# 13-DPLL-02.net
KiCad netlist of a schematic drawn in Altium Designer
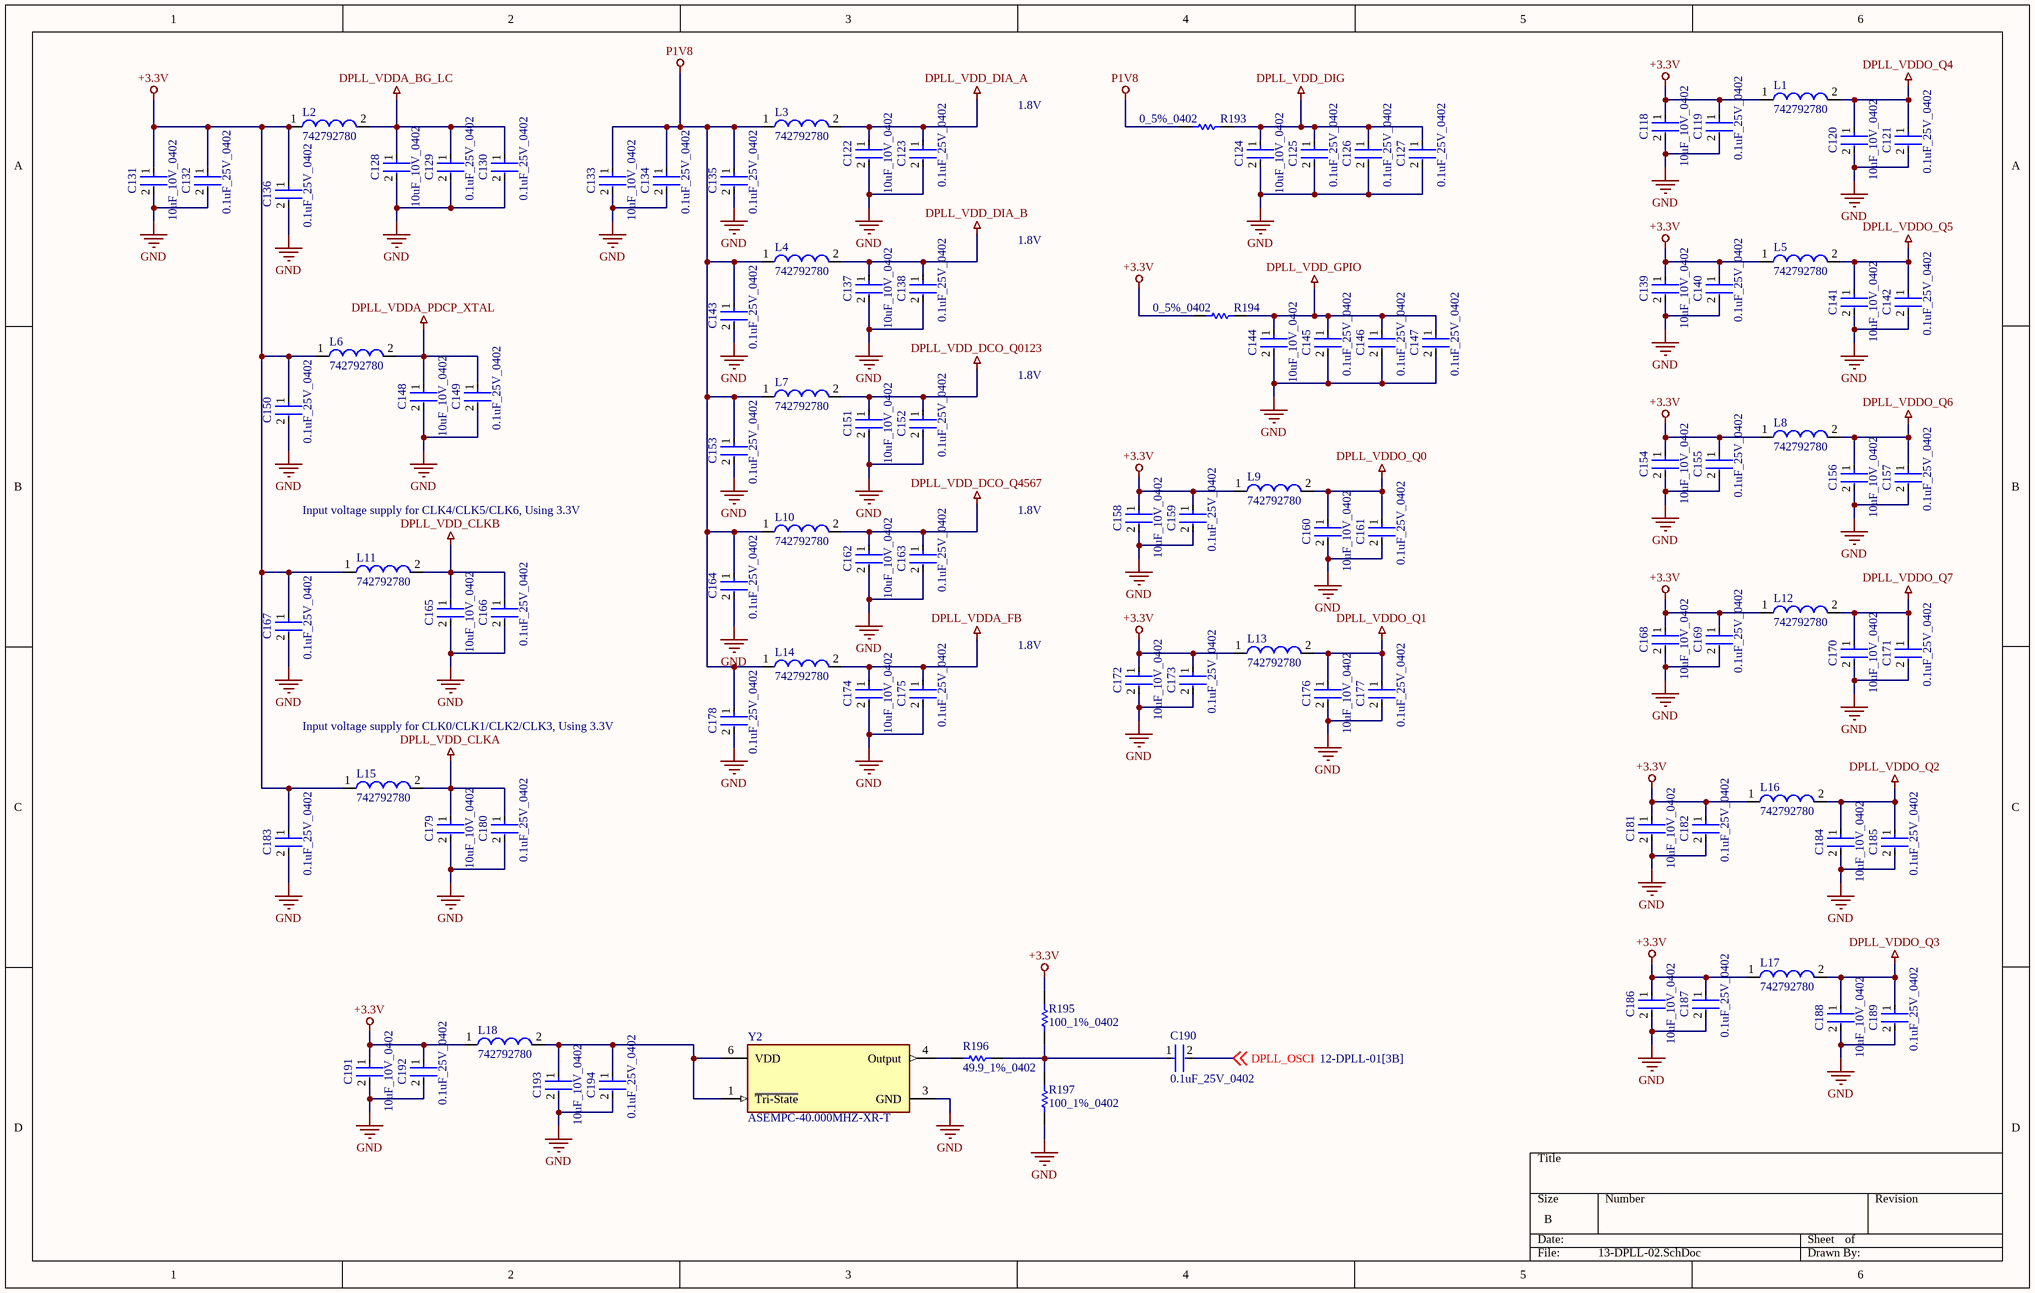
[diagram p0: 13-DPLL-02.SchDoc]

(export (version "E")
  (design (tool "Eeschema 10.0.6"))
  (components
    (comp (ref "C118")
      (value "10uF_10V_0402")
      (footprint "FP-CL05A106MP5NUNC-MFG")
      (description "CAP CER 10UF 10V X5R 0402")
      (fields
        (field (name "OCTOPART") "https://octopart.com/cl05a106mp5nunc-samsung-22457395")
        (field (name "TOLERANCE") "20%")
      )
      (libsource (lib "Altium Content Vault") (part "b4654b650e69147ec39a6b967a45e02"))
    )
    (comp (ref "C119")
      (value "0.1uF_25V_0402")
      (footprint "FP-0402-L_1_0_1-W_0_5_0_1-IPC_C")
      (description "General Purpose Ceramic Capacitor, 0402, 100nF, 10%, X7R, 15%, 25V")
      (fields (field (name "VOLTAGE") "25V") (field (name "TOLERANCE") "10%"))
      (libsource (lib "Altium Content Vault") (part "b4654b650e69147ec39a6b967a45e02"))
    )
    (comp (ref "C120")
      (value "10uF_10V_0402")
      (footprint "FP-CL05A106MP5NUNC-MFG")
      (description "CAP CER 10UF 10V X5R 0402")
      (fields
        (field (name "OCTOPART") "https://octopart.com/cl05a106mp5nunc-samsung-22457395")
        (field (name "TOLERANCE") "20%")
      )
      (libsource (lib "Altium Content Vault") (part "b4654b650e69147ec39a6b967a45e02"))
    )
    (comp (ref "C121")
      (value "0.1uF_25V_0402")
      (footprint "FP-0402-L_1_0_1-W_0_5_0_1-IPC_C")
      (description "General Purpose Ceramic Capacitor, 0402, 100nF, 10%, X7R, 15%, 25V")
      (fields (field (name "VOLTAGE") "25V") (field (name "TOLERANCE") "10%"))
      (libsource (lib "Altium Content Vault") (part "b4654b650e69147ec39a6b967a45e02"))
    )
    (comp (ref "C122")
      (value "10uF_10V_0402")
      (footprint "FP-CL05A106MP5NUNC-MFG")
      (description "CAP CER 10UF 10V X5R 0402")
      (fields
        (field (name "OCTOPART") "https://octopart.com/cl05a106mp5nunc-samsung-22457395")
        (field (name "TOLERANCE") "20%")
      )
      (libsource (lib "Altium Content Vault") (part "b4654b650e69147ec39a6b967a45e02"))
    )
    (comp (ref "C123")
      (value "0.1uF_25V_0402")
      (footprint "FP-0402-L_1_0_1-W_0_5_0_1-IPC_C")
      (description "General Purpose Ceramic Capacitor, 0402, 100nF, 10%, X7R, 15%, 25V")
      (fields (field (name "VOLTAGE") "25V") (field (name "TOLERANCE") "10%"))
      (libsource (lib "Altium Content Vault") (part "b4654b650e69147ec39a6b967a45e02"))
    )
    (comp (ref "C124")
      (value "10uF_10V_0402")
      (footprint "FP-CL05A106MP5NUNC-MFG")
      (description "CAP CER 10UF 10V X5R 0402")
      (fields
        (field (name "OCTOPART") "https://octopart.com/cl05a106mp5nunc-samsung-22457395")
        (field (name "TOLERANCE") "20%")
      )
      (libsource (lib "Altium Content Vault") (part "b4654b650e69147ec39a6b967a45e02"))
    )
    (comp (ref "C125")
      (value "0.1uF_25V_0402")
      (footprint "FP-0402-L_1_0_1-W_0_5_0_1-IPC_C")
      (description "General Purpose Ceramic Capacitor, 0402, 100nF, 10%, X7R, 15%, 25V")
      (fields (field (name "VOLTAGE") "25V") (field (name "TOLERANCE") "10%"))
      (libsource (lib "Altium Content Vault") (part "b4654b650e69147ec39a6b967a45e02"))
    )
    (comp (ref "C126")
      (value "0.1uF_25V_0402")
      (footprint "FP-0402-L_1_0_1-W_0_5_0_1-IPC_C")
      (description "General Purpose Ceramic Capacitor, 0402, 100nF, 10%, X7R, 15%, 25V")
      (fields (field (name "VOLTAGE") "25V") (field (name "TOLERANCE") "10%"))
      (libsource (lib "Altium Content Vault") (part "b4654b650e69147ec39a6b967a45e02"))
    )
    (comp (ref "C127")
      (value "0.1uF_25V_0402")
      (footprint "FP-0402-L_1_0_1-W_0_5_0_1-IPC_C")
      (description "General Purpose Ceramic Capacitor, 0402, 100nF, 10%, X7R, 15%, 25V")
      (fields (field (name "VOLTAGE") "25V") (field (name "TOLERANCE") "10%"))
      (libsource (lib "Altium Content Vault") (part "b4654b650e69147ec39a6b967a45e02"))
    )
    (comp (ref "C128")
      (value "10uF_10V_0402")
      (footprint "FP-CL05A106MP5NUNC-MFG")
      (description "CAP CER 10UF 10V X5R 0402")
      (fields
        (field (name "OCTOPART") "https://octopart.com/cl05a106mp5nunc-samsung-22457395")
        (field (name "TOLERANCE") "20%")
      )
      (libsource (lib "Altium Content Vault") (part "b4654b650e69147ec39a6b967a45e02"))
    )
    (comp (ref "C129")
      (value "0.1uF_25V_0402")
      (footprint "FP-0402-L_1_0_1-W_0_5_0_1-IPC_C")
      (description "General Purpose Ceramic Capacitor, 0402, 100nF, 10%, X7R, 15%, 25V")
      (fields (field (name "VOLTAGE") "25V") (field (name "TOLERANCE") "10%"))
      (libsource (lib "Altium Content Vault") (part "b4654b650e69147ec39a6b967a45e02"))
    )
    (comp (ref "C130")
      (value "0.1uF_25V_0402")
      (footprint "FP-0402-L_1_0_1-W_0_5_0_1-IPC_C")
      (description "General Purpose Ceramic Capacitor, 0402, 100nF, 10%, X7R, 15%, 25V")
      (fields (field (name "VOLTAGE") "25V") (field (name "TOLERANCE") "10%"))
      (libsource (lib "Altium Content Vault") (part "b4654b650e69147ec39a6b967a45e02"))
    )
    (comp (ref "C131")
      (value "10uF_10V_0402")
      (footprint "FP-CL05A106MP5NUNC-MFG")
      (description "CAP CER 10UF 10V X5R 0402")
      (fields
        (field (name "OCTOPART") "https://octopart.com/cl05a106mp5nunc-samsung-22457395")
        (field (name "TOLERANCE") "20%")
      )
      (libsource (lib "Altium Content Vault") (part "b4654b650e69147ec39a6b967a45e02"))
    )
    (comp (ref "C132")
      (value "0.1uF_25V_0402")
      (footprint "FP-0402-L_1_0_1-W_0_5_0_1-IPC_C")
      (description "General Purpose Ceramic Capacitor, 0402, 100nF, 10%, X7R, 15%, 25V")
      (fields (field (name "VOLTAGE") "25V") (field (name "TOLERANCE") "10%"))
      (libsource (lib "Altium Content Vault") (part "b4654b650e69147ec39a6b967a45e02"))
    )
    (comp (ref "C133")
      (value "10uF_10V_0402")
      (footprint "FP-CL05A106MP5NUNC-MFG")
      (description "CAP CER 10UF 10V X5R 0402")
      (fields
        (field (name "OCTOPART") "https://octopart.com/cl05a106mp5nunc-samsung-22457395")
        (field (name "TOLERANCE") "20%")
      )
      (libsource (lib "Altium Content Vault") (part "b4654b650e69147ec39a6b967a45e02"))
    )
    (comp (ref "C134")
      (value "0.1uF_25V_0402")
      (footprint "FP-0402-L_1_0_1-W_0_5_0_1-IPC_C")
      (description "General Purpose Ceramic Capacitor, 0402, 100nF, 10%, X7R, 15%, 25V")
      (fields (field (name "VOLTAGE") "25V") (field (name "TOLERANCE") "10%"))
      (libsource (lib "Altium Content Vault") (part "b4654b650e69147ec39a6b967a45e02"))
    )
    (comp (ref "C135")
      (value "0.1uF_25V_0402")
      (footprint "FP-0402-L_1_0_1-W_0_5_0_1-IPC_C")
      (description "General Purpose Ceramic Capacitor, 0402, 100nF, 10%, X7R, 15%, 25V")
      (fields (field (name "VOLTAGE") "25V") (field (name "TOLERANCE") "10%"))
      (libsource (lib "Altium Content Vault") (part "b4654b650e69147ec39a6b967a45e02"))
    )
    (comp (ref "C136")
      (value "0.1uF_25V_0402")
      (footprint "FP-0402-L_1_0_1-W_0_5_0_1-IPC_C")
      (description "General Purpose Ceramic Capacitor, 0402, 100nF, 10%, X7R, 15%, 25V")
      (fields (field (name "VOLTAGE") "25V") (field (name "TOLERANCE") "10%"))
      (libsource (lib "Altium Content Vault") (part "b4654b650e69147ec39a6b967a45e02"))
    )
    (comp (ref "C137")
      (value "10uF_10V_0402")
      (footprint "FP-CL05A106MP5NUNC-MFG")
      (description "CAP CER 10UF 10V X5R 0402")
      (fields
        (field (name "OCTOPART") "https://octopart.com/cl05a106mp5nunc-samsung-22457395")
        (field (name "TOLERANCE") "20%")
      )
      (libsource (lib "Altium Content Vault") (part "b4654b650e69147ec39a6b967a45e02"))
    )
    (comp (ref "C138")
      (value "0.1uF_25V_0402")
      (footprint "FP-0402-L_1_0_1-W_0_5_0_1-IPC_C")
      (description "General Purpose Ceramic Capacitor, 0402, 100nF, 10%, X7R, 15%, 25V")
      (fields (field (name "VOLTAGE") "25V") (field (name "TOLERANCE") "10%"))
      (libsource (lib "Altium Content Vault") (part "b4654b650e69147ec39a6b967a45e02"))
    )
    (comp (ref "C139")
      (value "10uF_10V_0402")
      (footprint "FP-CL05A106MP5NUNC-MFG")
      (description "CAP CER 10UF 10V X5R 0402")
      (fields
        (field (name "OCTOPART") "https://octopart.com/cl05a106mp5nunc-samsung-22457395")
        (field (name "TOLERANCE") "20%")
      )
      (libsource (lib "Altium Content Vault") (part "b4654b650e69147ec39a6b967a45e02"))
    )
    (comp (ref "C140")
      (value "0.1uF_25V_0402")
      (footprint "FP-0402-L_1_0_1-W_0_5_0_1-IPC_C")
      (description "General Purpose Ceramic Capacitor, 0402, 100nF, 10%, X7R, 15%, 25V")
      (fields (field (name "VOLTAGE") "25V") (field (name "TOLERANCE") "10%"))
      (libsource (lib "Altium Content Vault") (part "b4654b650e69147ec39a6b967a45e02"))
    )
    (comp (ref "C141")
      (value "10uF_10V_0402")
      (footprint "FP-CL05A106MP5NUNC-MFG")
      (description "CAP CER 10UF 10V X5R 0402")
      (fields
        (field (name "OCTOPART") "https://octopart.com/cl05a106mp5nunc-samsung-22457395")
        (field (name "TOLERANCE") "20%")
      )
      (libsource (lib "Altium Content Vault") (part "b4654b650e69147ec39a6b967a45e02"))
    )
    (comp (ref "C142")
      (value "0.1uF_25V_0402")
      (footprint "FP-0402-L_1_0_1-W_0_5_0_1-IPC_C")
      (description "General Purpose Ceramic Capacitor, 0402, 100nF, 10%, X7R, 15%, 25V")
      (fields (field (name "VOLTAGE") "25V") (field (name "TOLERANCE") "10%"))
      (libsource (lib "Altium Content Vault") (part "b4654b650e69147ec39a6b967a45e02"))
    )
    (comp (ref "C143")
      (value "0.1uF_25V_0402")
      (footprint "FP-0402-L_1_0_1-W_0_5_0_1-IPC_C")
      (description "General Purpose Ceramic Capacitor, 0402, 100nF, 10%, X7R, 15%, 25V")
      (fields (field (name "VOLTAGE") "25V") (field (name "TOLERANCE") "10%"))
      (libsource (lib "Altium Content Vault") (part "b4654b650e69147ec39a6b967a45e02"))
    )
    (comp (ref "C144")
      (value "10uF_10V_0402")
      (footprint "FP-CL05A106MP5NUNC-MFG")
      (description "CAP CER 10UF 10V X5R 0402")
      (fields
        (field (name "OCTOPART") "https://octopart.com/cl05a106mp5nunc-samsung-22457395")
        (field (name "TOLERANCE") "20%")
      )
      (libsource (lib "Altium Content Vault") (part "b4654b650e69147ec39a6b967a45e02"))
    )
    (comp (ref "C145")
      (value "0.1uF_25V_0402")
      (footprint "FP-0402-L_1_0_1-W_0_5_0_1-IPC_C")
      (description "General Purpose Ceramic Capacitor, 0402, 100nF, 10%, X7R, 15%, 25V")
      (fields (field (name "VOLTAGE") "25V") (field (name "TOLERANCE") "10%"))
      (libsource (lib "Altium Content Vault") (part "b4654b650e69147ec39a6b967a45e02"))
    )
    (comp (ref "C146")
      (value "0.1uF_25V_0402")
      (footprint "FP-0402-L_1_0_1-W_0_5_0_1-IPC_C")
      (description "General Purpose Ceramic Capacitor, 0402, 100nF, 10%, X7R, 15%, 25V")
      (fields (field (name "VOLTAGE") "25V") (field (name "TOLERANCE") "10%"))
      (libsource (lib "Altium Content Vault") (part "b4654b650e69147ec39a6b967a45e02"))
    )
    (comp (ref "C147")
      (value "0.1uF_25V_0402")
      (footprint "FP-0402-L_1_0_1-W_0_5_0_1-IPC_C")
      (description "General Purpose Ceramic Capacitor, 0402, 100nF, 10%, X7R, 15%, 25V")
      (fields (field (name "VOLTAGE") "25V") (field (name "TOLERANCE") "10%"))
      (libsource (lib "Altium Content Vault") (part "b4654b650e69147ec39a6b967a45e02"))
    )
    (comp (ref "C148")
      (value "10uF_10V_0402")
      (footprint "FP-CL05A106MP5NUNC-MFG")
      (description "CAP CER 10UF 10V X5R 0402")
      (fields
        (field (name "OCTOPART") "https://octopart.com/cl05a106mp5nunc-samsung-22457395")
        (field (name "TOLERANCE") "20%")
      )
      (libsource (lib "Altium Content Vault") (part "b4654b650e69147ec39a6b967a45e02"))
    )
    (comp (ref "C149")
      (value "0.1uF_25V_0402")
      (footprint "FP-0402-L_1_0_1-W_0_5_0_1-IPC_C")
      (description "General Purpose Ceramic Capacitor, 0402, 100nF, 10%, X7R, 15%, 25V")
      (fields (field (name "VOLTAGE") "25V") (field (name "TOLERANCE") "10%"))
      (libsource (lib "Altium Content Vault") (part "b4654b650e69147ec39a6b967a45e02"))
    )
    (comp (ref "C150")
      (value "0.1uF_25V_0402")
      (footprint "FP-0402-L_1_0_1-W_0_5_0_1-IPC_C")
      (description "General Purpose Ceramic Capacitor, 0402, 100nF, 10%, X7R, 15%, 25V")
      (fields (field (name "VOLTAGE") "25V") (field (name "TOLERANCE") "10%"))
      (libsource (lib "Altium Content Vault") (part "b4654b650e69147ec39a6b967a45e02"))
    )
    (comp (ref "C151")
      (value "10uF_10V_0402")
      (footprint "FP-CL05A106MP5NUNC-MFG")
      (description "CAP CER 10UF 10V X5R 0402")
      (fields
        (field (name "OCTOPART") "https://octopart.com/cl05a106mp5nunc-samsung-22457395")
        (field (name "TOLERANCE") "20%")
      )
      (libsource (lib "Altium Content Vault") (part "b4654b650e69147ec39a6b967a45e02"))
    )
    (comp (ref "C152")
      (value "0.1uF_25V_0402")
      (footprint "FP-0402-L_1_0_1-W_0_5_0_1-IPC_C")
      (description "General Purpose Ceramic Capacitor, 0402, 100nF, 10%, X7R, 15%, 25V")
      (fields (field (name "VOLTAGE") "25V") (field (name "TOLERANCE") "10%"))
      (libsource (lib "Altium Content Vault") (part "b4654b650e69147ec39a6b967a45e02"))
    )
    (comp (ref "C153")
      (value "0.1uF_25V_0402")
      (footprint "FP-0402-L_1_0_1-W_0_5_0_1-IPC_C")
      (description "General Purpose Ceramic Capacitor, 0402, 100nF, 10%, X7R, 15%, 25V")
      (fields (field (name "VOLTAGE") "25V") (field (name "TOLERANCE") "10%"))
      (libsource (lib "Altium Content Vault") (part "b4654b650e69147ec39a6b967a45e02"))
    )
    (comp (ref "C154")
      (value "10uF_10V_0402")
      (footprint "FP-CL05A106MP5NUNC-MFG")
      (description "CAP CER 10UF 10V X5R 0402")
      (fields
        (field (name "OCTOPART") "https://octopart.com/cl05a106mp5nunc-samsung-22457395")
        (field (name "TOLERANCE") "20%")
      )
      (libsource (lib "Altium Content Vault") (part "b4654b650e69147ec39a6b967a45e02"))
    )
    (comp (ref "C155")
      (value "0.1uF_25V_0402")
      (footprint "FP-0402-L_1_0_1-W_0_5_0_1-IPC_C")
      (description "General Purpose Ceramic Capacitor, 0402, 100nF, 10%, X7R, 15%, 25V")
      (fields (field (name "VOLTAGE") "25V") (field (name "TOLERANCE") "10%"))
      (libsource (lib "Altium Content Vault") (part "b4654b650e69147ec39a6b967a45e02"))
    )
    (comp (ref "C156")
      (value "10uF_10V_0402")
      (footprint "FP-CL05A106MP5NUNC-MFG")
      (description "CAP CER 10UF 10V X5R 0402")
      (fields
        (field (name "OCTOPART") "https://octopart.com/cl05a106mp5nunc-samsung-22457395")
        (field (name "TOLERANCE") "20%")
      )
      (libsource (lib "Altium Content Vault") (part "b4654b650e69147ec39a6b967a45e02"))
    )
    (comp (ref "C157")
      (value "0.1uF_25V_0402")
      (footprint "FP-0402-L_1_0_1-W_0_5_0_1-IPC_C")
      (description "General Purpose Ceramic Capacitor, 0402, 100nF, 10%, X7R, 15%, 25V")
      (fields (field (name "VOLTAGE") "25V") (field (name "TOLERANCE") "10%"))
      (libsource (lib "Altium Content Vault") (part "b4654b650e69147ec39a6b967a45e02"))
    )
    (comp (ref "C158")
      (value "10uF_10V_0402")
      (footprint "FP-CL05A106MP5NUNC-MFG")
      (description "CAP CER 10UF 10V X5R 0402")
      (fields
        (field (name "OCTOPART") "https://octopart.com/cl05a106mp5nunc-samsung-22457395")
        (field (name "TOLERANCE") "20%")
      )
      (libsource (lib "Altium Content Vault") (part "b4654b650e69147ec39a6b967a45e02"))
    )
    (comp (ref "C159")
      (value "0.1uF_25V_0402")
      (footprint "FP-0402-L_1_0_1-W_0_5_0_1-IPC_C")
      (description "General Purpose Ceramic Capacitor, 0402, 100nF, 10%, X7R, 15%, 25V")
      (fields (field (name "VOLTAGE") "25V") (field (name "TOLERANCE") "10%"))
      (libsource (lib "Altium Content Vault") (part "b4654b650e69147ec39a6b967a45e02"))
    )
    (comp (ref "C160")
      (value "10uF_10V_0402")
      (footprint "FP-CL05A106MP5NUNC-MFG")
      (description "CAP CER 10UF 10V X5R 0402")
      (fields
        (field (name "OCTOPART") "https://octopart.com/cl05a106mp5nunc-samsung-22457395")
        (field (name "TOLERANCE") "20%")
      )
      (libsource (lib "Altium Content Vault") (part "b4654b650e69147ec39a6b967a45e02"))
    )
    (comp (ref "C161")
      (value "0.1uF_25V_0402")
      (footprint "FP-0402-L_1_0_1-W_0_5_0_1-IPC_C")
      (description "General Purpose Ceramic Capacitor, 0402, 100nF, 10%, X7R, 15%, 25V")
      (fields (field (name "VOLTAGE") "25V") (field (name "TOLERANCE") "10%"))
      (libsource (lib "Altium Content Vault") (part "b4654b650e69147ec39a6b967a45e02"))
    )
    (comp (ref "C162")
      (value "10uF_10V_0402")
      (footprint "FP-CL05A106MP5NUNC-MFG")
      (description "CAP CER 10UF 10V X5R 0402")
      (fields
        (field (name "OCTOPART") "https://octopart.com/cl05a106mp5nunc-samsung-22457395")
        (field (name "TOLERANCE") "20%")
      )
      (libsource (lib "Altium Content Vault") (part "b4654b650e69147ec39a6b967a45e02"))
    )
    (comp (ref "C163")
      (value "0.1uF_25V_0402")
      (footprint "FP-0402-L_1_0_1-W_0_5_0_1-IPC_C")
      (description "General Purpose Ceramic Capacitor, 0402, 100nF, 10%, X7R, 15%, 25V")
      (fields (field (name "VOLTAGE") "25V") (field (name "TOLERANCE") "10%"))
      (libsource (lib "Altium Content Vault") (part "b4654b650e69147ec39a6b967a45e02"))
    )
    (comp (ref "C164")
      (value "0.1uF_25V_0402")
      (footprint "FP-0402-L_1_0_1-W_0_5_0_1-IPC_C")
      (description "General Purpose Ceramic Capacitor, 0402, 100nF, 10%, X7R, 15%, 25V")
      (fields (field (name "VOLTAGE") "25V") (field (name "TOLERANCE") "10%"))
      (libsource (lib "Altium Content Vault") (part "b4654b650e69147ec39a6b967a45e02"))
    )
    (comp (ref "C165")
      (value "10uF_10V_0402")
      (footprint "FP-CL05A106MP5NUNC-MFG")
      (description "CAP CER 10UF 10V X5R 0402")
      (fields
        (field (name "OCTOPART") "https://octopart.com/cl05a106mp5nunc-samsung-22457395")
        (field (name "TOLERANCE") "20%")
      )
      (libsource (lib "Altium Content Vault") (part "b4654b650e69147ec39a6b967a45e02"))
    )
    (comp (ref "C166")
      (value "0.1uF_25V_0402")
      (footprint "FP-0402-L_1_0_1-W_0_5_0_1-IPC_C")
      (description "General Purpose Ceramic Capacitor, 0402, 100nF, 10%, X7R, 15%, 25V")
      (fields (field (name "VOLTAGE") "25V") (field (name "TOLERANCE") "10%"))
      (libsource (lib "Altium Content Vault") (part "b4654b650e69147ec39a6b967a45e02"))
    )
    (comp (ref "C167")
      (value "0.1uF_25V_0402")
      (footprint "FP-0402-L_1_0_1-W_0_5_0_1-IPC_C")
      (description "General Purpose Ceramic Capacitor, 0402, 100nF, 10%, X7R, 15%, 25V")
      (fields (field (name "VOLTAGE") "25V") (field (name "TOLERANCE") "10%"))
      (libsource (lib "Altium Content Vault") (part "b4654b650e69147ec39a6b967a45e02"))
    )
    (comp (ref "C168")
      (value "10uF_10V_0402")
      (footprint "FP-CL05A106MP5NUNC-MFG")
      (description "CAP CER 10UF 10V X5R 0402")
      (fields
        (field (name "OCTOPART") "https://octopart.com/cl05a106mp5nunc-samsung-22457395")
        (field (name "TOLERANCE") "20%")
      )
      (libsource (lib "Altium Content Vault") (part "b4654b650e69147ec39a6b967a45e02"))
    )
    (comp (ref "C169")
      (value "0.1uF_25V_0402")
      (footprint "FP-0402-L_1_0_1-W_0_5_0_1-IPC_C")
      (description "General Purpose Ceramic Capacitor, 0402, 100nF, 10%, X7R, 15%, 25V")
      (fields (field (name "VOLTAGE") "25V") (field (name "TOLERANCE") "10%"))
      (libsource (lib "Altium Content Vault") (part "b4654b650e69147ec39a6b967a45e02"))
    )
    (comp (ref "C170")
      (value "10uF_10V_0402")
      (footprint "FP-CL05A106MP5NUNC-MFG")
      (description "CAP CER 10UF 10V X5R 0402")
      (fields
        (field (name "OCTOPART") "https://octopart.com/cl05a106mp5nunc-samsung-22457395")
        (field (name "TOLERANCE") "20%")
      )
      (libsource (lib "Altium Content Vault") (part "b4654b650e69147ec39a6b967a45e02"))
    )
    (comp (ref "C171")
      (value "0.1uF_25V_0402")
      (footprint "FP-0402-L_1_0_1-W_0_5_0_1-IPC_C")
      (description "General Purpose Ceramic Capacitor, 0402, 100nF, 10%, X7R, 15%, 25V")
      (fields (field (name "VOLTAGE") "25V") (field (name "TOLERANCE") "10%"))
      (libsource (lib "Altium Content Vault") (part "b4654b650e69147ec39a6b967a45e02"))
    )
    (comp (ref "C172")
      (value "10uF_10V_0402")
      (footprint "FP-CL05A106MP5NUNC-MFG")
      (description "CAP CER 10UF 10V X5R 0402")
      (fields
        (field (name "OCTOPART") "https://octopart.com/cl05a106mp5nunc-samsung-22457395")
        (field (name "TOLERANCE") "20%")
      )
      (libsource (lib "Altium Content Vault") (part "b4654b650e69147ec39a6b967a45e02"))
    )
    (comp (ref "C173")
      (value "0.1uF_25V_0402")
      (footprint "FP-0402-L_1_0_1-W_0_5_0_1-IPC_C")
      (description "General Purpose Ceramic Capacitor, 0402, 100nF, 10%, X7R, 15%, 25V")
      (fields (field (name "VOLTAGE") "25V") (field (name "TOLERANCE") "10%"))
      (libsource (lib "Altium Content Vault") (part "b4654b650e69147ec39a6b967a45e02"))
    )
    (comp (ref "C174")
      (value "10uF_10V_0402")
      (footprint "FP-CL05A106MP5NUNC-MFG")
      (description "CAP CER 10UF 10V X5R 0402")
      (fields
        (field (name "OCTOPART") "https://octopart.com/cl05a106mp5nunc-samsung-22457395")
        (field (name "TOLERANCE") "20%")
      )
      (libsource (lib "Altium Content Vault") (part "b4654b650e69147ec39a6b967a45e02"))
    )
    (comp (ref "C175")
      (value "0.1uF_25V_0402")
      (footprint "FP-0402-L_1_0_1-W_0_5_0_1-IPC_C")
      (description "General Purpose Ceramic Capacitor, 0402, 100nF, 10%, X7R, 15%, 25V")
      (fields (field (name "VOLTAGE") "25V") (field (name "TOLERANCE") "10%"))
      (libsource (lib "Altium Content Vault") (part "b4654b650e69147ec39a6b967a45e02"))
    )
    (comp (ref "C176")
      (value "10uF_10V_0402")
      (footprint "FP-CL05A106MP5NUNC-MFG")
      (description "CAP CER 10UF 10V X5R 0402")
      (fields
        (field (name "OCTOPART") "https://octopart.com/cl05a106mp5nunc-samsung-22457395")
        (field (name "TOLERANCE") "20%")
      )
      (libsource (lib "Altium Content Vault") (part "b4654b650e69147ec39a6b967a45e02"))
    )
    (comp (ref "C177")
      (value "0.1uF_25V_0402")
      (footprint "FP-0402-L_1_0_1-W_0_5_0_1-IPC_C")
      (description "General Purpose Ceramic Capacitor, 0402, 100nF, 10%, X7R, 15%, 25V")
      (fields (field (name "VOLTAGE") "25V") (field (name "TOLERANCE") "10%"))
      (libsource (lib "Altium Content Vault") (part "b4654b650e69147ec39a6b967a45e02"))
    )
    (comp (ref "C178")
      (value "0.1uF_25V_0402")
      (footprint "FP-0402-L_1_0_1-W_0_5_0_1-IPC_C")
      (description "General Purpose Ceramic Capacitor, 0402, 100nF, 10%, X7R, 15%, 25V")
      (fields (field (name "VOLTAGE") "25V") (field (name "TOLERANCE") "10%"))
      (libsource (lib "Altium Content Vault") (part "b4654b650e69147ec39a6b967a45e02"))
    )
    (comp (ref "C179")
      (value "10uF_10V_0402")
      (footprint "FP-CL05A106MP5NUNC-MFG")
      (description "CAP CER 10UF 10V X5R 0402")
      (fields
        (field (name "OCTOPART") "https://octopart.com/cl05a106mp5nunc-samsung-22457395")
        (field (name "TOLERANCE") "20%")
      )
      (libsource (lib "Altium Content Vault") (part "b4654b650e69147ec39a6b967a45e02"))
    )
    (comp (ref "C180")
      (value "0.1uF_25V_0402")
      (footprint "FP-0402-L_1_0_1-W_0_5_0_1-IPC_C")
      (description "General Purpose Ceramic Capacitor, 0402, 100nF, 10%, X7R, 15%, 25V")
      (fields (field (name "VOLTAGE") "25V") (field (name "TOLERANCE") "10%"))
      (libsource (lib "Altium Content Vault") (part "b4654b650e69147ec39a6b967a45e02"))
    )
    (comp (ref "C181")
      (value "10uF_10V_0402")
      (footprint "FP-CL05A106MP5NUNC-MFG")
      (description "CAP CER 10UF 10V X5R 0402")
      (fields
        (field (name "OCTOPART") "https://octopart.com/cl05a106mp5nunc-samsung-22457395")
        (field (name "TOLERANCE") "20%")
      )
      (libsource (lib "Altium Content Vault") (part "b4654b650e69147ec39a6b967a45e02"))
    )
    (comp (ref "C182")
      (value "0.1uF_25V_0402")
      (footprint "FP-0402-L_1_0_1-W_0_5_0_1-IPC_C")
      (description "General Purpose Ceramic Capacitor, 0402, 100nF, 10%, X7R, 15%, 25V")
      (fields (field (name "VOLTAGE") "25V") (field (name "TOLERANCE") "10%"))
      (libsource (lib "Altium Content Vault") (part "b4654b650e69147ec39a6b967a45e02"))
    )
    (comp (ref "C183")
      (value "0.1uF_25V_0402")
      (footprint "FP-0402-L_1_0_1-W_0_5_0_1-IPC_C")
      (description "General Purpose Ceramic Capacitor, 0402, 100nF, 10%, X7R, 15%, 25V")
      (fields (field (name "VOLTAGE") "25V") (field (name "TOLERANCE") "10%"))
      (libsource (lib "Altium Content Vault") (part "b4654b650e69147ec39a6b967a45e02"))
    )
    (comp (ref "C184")
      (value "10uF_10V_0402")
      (footprint "FP-CL05A106MP5NUNC-MFG")
      (description "CAP CER 10UF 10V X5R 0402")
      (fields
        (field (name "OCTOPART") "https://octopart.com/cl05a106mp5nunc-samsung-22457395")
        (field (name "TOLERANCE") "20%")
      )
      (libsource (lib "Altium Content Vault") (part "b4654b650e69147ec39a6b967a45e02"))
    )
    (comp (ref "C185")
      (value "0.1uF_25V_0402")
      (footprint "FP-0402-L_1_0_1-W_0_5_0_1-IPC_C")
      (description "General Purpose Ceramic Capacitor, 0402, 100nF, 10%, X7R, 15%, 25V")
      (fields (field (name "VOLTAGE") "25V") (field (name "TOLERANCE") "10%"))
      (libsource (lib "Altium Content Vault") (part "b4654b650e69147ec39a6b967a45e02"))
    )
    (comp (ref "C186")
      (value "10uF_10V_0402")
      (footprint "FP-CL05A106MP5NUNC-MFG")
      (description "CAP CER 10UF 10V X5R 0402")
      (fields
        (field (name "OCTOPART") "https://octopart.com/cl05a106mp5nunc-samsung-22457395")
        (field (name "TOLERANCE") "20%")
      )
      (libsource (lib "Altium Content Vault") (part "b4654b650e69147ec39a6b967a45e02"))
    )
    (comp (ref "C187")
      (value "0.1uF_25V_0402")
      (footprint "FP-0402-L_1_0_1-W_0_5_0_1-IPC_C")
      (description "General Purpose Ceramic Capacitor, 0402, 100nF, 10%, X7R, 15%, 25V")
      (fields (field (name "VOLTAGE") "25V") (field (name "TOLERANCE") "10%"))
      (libsource (lib "Altium Content Vault") (part "b4654b650e69147ec39a6b967a45e02"))
    )
    (comp (ref "C188")
      (value "10uF_10V_0402")
      (footprint "FP-CL05A106MP5NUNC-MFG")
      (description "CAP CER 10UF 10V X5R 0402")
      (fields
        (field (name "OCTOPART") "https://octopart.com/cl05a106mp5nunc-samsung-22457395")
        (field (name "TOLERANCE") "20%")
      )
      (libsource (lib "Altium Content Vault") (part "b4654b650e69147ec39a6b967a45e02"))
    )
    (comp (ref "C189")
      (value "0.1uF_25V_0402")
      (footprint "FP-0402-L_1_0_1-W_0_5_0_1-IPC_C")
      (description "General Purpose Ceramic Capacitor, 0402, 100nF, 10%, X7R, 15%, 25V")
      (fields (field (name "VOLTAGE") "25V") (field (name "TOLERANCE") "10%"))
      (libsource (lib "Altium Content Vault") (part "b4654b650e69147ec39a6b967a45e02"))
    )
    (comp (ref "C190")
      (value "0.1uF_25V_0402")
      (footprint "FP-0402-L_1_0_1-W_0_5_0_1-IPC_C")
      (description "General Purpose Ceramic Capacitor, 0402, 100nF, 10%, X7R, 15%, 25V")
      (fields (field (name "VOLTAGE") "25V") (field (name "TOLERANCE") "10%"))
      (libsource (lib "Altium Content Vault") (part "b4654b650e69147ec39a6b967a45e02"))
    )
    (comp (ref "C191")
      (value "10uF_10V_0402")
      (footprint "FP-CL05A106MP5NUNC-MFG")
      (description "CAP CER 10UF 10V X5R 0402")
      (fields
        (field (name "OCTOPART") "https://octopart.com/cl05a106mp5nunc-samsung-22457395")
        (field (name "TOLERANCE") "20%")
      )
      (libsource (lib "Altium Content Vault") (part "b4654b650e69147ec39a6b967a45e02"))
    )
    (comp (ref "C192")
      (value "0.1uF_25V_0402")
      (footprint "FP-0402-L_1_0_1-W_0_5_0_1-IPC_C")
      (description "General Purpose Ceramic Capacitor, 0402, 100nF, 10%, X7R, 15%, 25V")
      (fields (field (name "VOLTAGE") "25V") (field (name "TOLERANCE") "10%"))
      (libsource (lib "Altium Content Vault") (part "b4654b650e69147ec39a6b967a45e02"))
    )
    (comp (ref "C193")
      (value "10uF_10V_0402")
      (footprint "FP-CL05A106MP5NUNC-MFG")
      (description "CAP CER 10UF 10V X5R 0402")
      (fields
        (field (name "OCTOPART") "https://octopart.com/cl05a106mp5nunc-samsung-22457395")
        (field (name "TOLERANCE") "20%")
      )
      (libsource (lib "Altium Content Vault") (part "b4654b650e69147ec39a6b967a45e02"))
    )
    (comp (ref "C194")
      (value "0.1uF_25V_0402")
      (footprint "FP-0402-L_1_0_1-W_0_5_0_1-IPC_C")
      (description "General Purpose Ceramic Capacitor, 0402, 100nF, 10%, X7R, 15%, 25V")
      (fields (field (name "VOLTAGE") "25V") (field (name "TOLERANCE") "10%"))
      (libsource (lib "Altium Content Vault") (part "b4654b650e69147ec39a6b967a45e02"))
    )
    (comp (ref "L1")
      (value "742792780")
      (footprint "SMD-0402")
      (description "SMD EMI Suppression Ferrite Bead WE-CBF, Z = 220 Ohm")
      (libsource (lib "Altium Content Vault") (part "PAS-IND-INDUCTOR-2"))
    )
    (comp (ref "L2")
      (value "742792780")
      (footprint "SMD-0402")
      (description "SMD EMI Suppression Ferrite Bead WE-CBF, Z = 220 Ohm")
      (libsource (lib "Altium Content Vault") (part "PAS-IND-INDUCTOR-2"))
    )
    (comp (ref "L3")
      (value "742792780")
      (footprint "SMD-0402")
      (description "SMD EMI Suppression Ferrite Bead WE-CBF, Z = 220 Ohm")
      (libsource (lib "Altium Content Vault") (part "PAS-IND-INDUCTOR-2"))
    )
    (comp (ref "L4")
      (value "742792780")
      (footprint "SMD-0402")
      (description "SMD EMI Suppression Ferrite Bead WE-CBF, Z = 220 Ohm")
      (libsource (lib "Altium Content Vault") (part "PAS-IND-INDUCTOR-2"))
    )
    (comp (ref "L5")
      (value "742792780")
      (footprint "SMD-0402")
      (description "SMD EMI Suppression Ferrite Bead WE-CBF, Z = 220 Ohm")
      (libsource (lib "Altium Content Vault") (part "PAS-IND-INDUCTOR-2"))
    )
    (comp (ref "L6")
      (value "742792780")
      (footprint "SMD-0402")
      (description "SMD EMI Suppression Ferrite Bead WE-CBF, Z = 220 Ohm")
      (libsource (lib "Altium Content Vault") (part "PAS-IND-INDUCTOR-2"))
    )
    (comp (ref "L7")
      (value "742792780")
      (footprint "SMD-0402")
      (description "SMD EMI Suppression Ferrite Bead WE-CBF, Z = 220 Ohm")
      (libsource (lib "Altium Content Vault") (part "PAS-IND-INDUCTOR-2"))
    )
    (comp (ref "L8")
      (value "742792780")
      (footprint "SMD-0402")
      (description "SMD EMI Suppression Ferrite Bead WE-CBF, Z = 220 Ohm")
      (libsource (lib "Altium Content Vault") (part "PAS-IND-INDUCTOR-2"))
    )
    (comp (ref "L9")
      (value "742792780")
      (footprint "SMD-0402")
      (description "SMD EMI Suppression Ferrite Bead WE-CBF, Z = 220 Ohm")
      (libsource (lib "Altium Content Vault") (part "PAS-IND-INDUCTOR-2"))
    )
    (comp (ref "L10")
      (value "742792780")
      (footprint "SMD-0402")
      (description "SMD EMI Suppression Ferrite Bead WE-CBF, Z = 220 Ohm")
      (libsource (lib "Altium Content Vault") (part "PAS-IND-INDUCTOR-2"))
    )
    (comp (ref "L11")
      (value "742792780")
      (footprint "SMD-0402")
      (description "SMD EMI Suppression Ferrite Bead WE-CBF, Z = 220 Ohm")
      (libsource (lib "Altium Content Vault") (part "PAS-IND-INDUCTOR-2"))
    )
    (comp (ref "L12")
      (value "742792780")
      (footprint "SMD-0402")
      (description "SMD EMI Suppression Ferrite Bead WE-CBF, Z = 220 Ohm")
      (libsource (lib "Altium Content Vault") (part "PAS-IND-INDUCTOR-2"))
    )
    (comp (ref "L13")
      (value "742792780")
      (footprint "SMD-0402")
      (description "SMD EMI Suppression Ferrite Bead WE-CBF, Z = 220 Ohm")
      (libsource (lib "Altium Content Vault") (part "PAS-IND-INDUCTOR-2"))
    )
    (comp (ref "L14")
      (value "742792780")
      (footprint "SMD-0402")
      (description "SMD EMI Suppression Ferrite Bead WE-CBF, Z = 220 Ohm")
      (libsource (lib "Altium Content Vault") (part "PAS-IND-INDUCTOR-2"))
    )
    (comp (ref "L15")
      (value "742792780")
      (footprint "SMD-0402")
      (description "SMD EMI Suppression Ferrite Bead WE-CBF, Z = 220 Ohm")
      (libsource (lib "Altium Content Vault") (part "PAS-IND-INDUCTOR-2"))
    )
    (comp (ref "L16")
      (value "742792780")
      (footprint "SMD-0402")
      (description "SMD EMI Suppression Ferrite Bead WE-CBF, Z = 220 Ohm")
      (libsource (lib "Altium Content Vault") (part "PAS-IND-INDUCTOR-2"))
    )
    (comp (ref "L17")
      (value "742792780")
      (footprint "SMD-0402")
      (description "SMD EMI Suppression Ferrite Bead WE-CBF, Z = 220 Ohm")
      (libsource (lib "Altium Content Vault") (part "PAS-IND-INDUCTOR-2"))
    )
    (comp (ref "L18")
      (value "742792780")
      (footprint "SMD-0402")
      (description "SMD EMI Suppression Ferrite Bead WE-CBF, Z = 220 Ohm")
      (libsource (lib "Altium Content Vault") (part "PAS-IND-INDUCTOR-2"))
    )
    (comp (ref "R193")
      (value "0_5%_0402")
      (footprint "RESC1005X40X25LL10T10")
      (fields (field (name "MANUFACTURER") "KOA Speer") (field (name "PART NUMBER") "RK73Z1ETTP"))
      (libsource (lib "Altium Content Vault") (part "RES"))
    )
    (comp (ref "R194")
      (value "0_5%_0402")
      (footprint "RESC1005X40X25LL10T10")
      (fields (field (name "MANUFACTURER") "KOA Speer") (field (name "PART NUMBER") "RK73Z1ETTP"))
      (libsource (lib "Altium Content Vault") (part "RES"))
    )
    (comp (ref "R195")
      (value "100_1%_0402")
      (footprint "RESC1005X40X25ML05T10")
      (fields (field (name "PART NUMBER") "ERJ-U02F1000X") (field (name "MANUFACTURER") "Panasonic"))
      (libsource (lib "Altium Content Vault") (part "RES"))
    )
    (comp (ref "R196")
      (value "49.9_1%_0402")
      (footprint "RESC1005X40X25NL10T10")
      (fields (field (name "PART NUMBER") "RK73H1ETTP49R9F") (field (name "MANUFACTURER") "KOA Speer"))
      (libsource (lib "Altium Content Vault") (part "RES"))
    )
    (comp (ref "R197")
      (value "100_1%_0402")
      (footprint "RESC1005X40X25ML05T10")
      (fields (field (name "PART NUMBER") "ERJ-U02F1000X") (field (name "MANUFACTURER") "Panasonic"))
      (libsource (lib "Altium Content Vault") (part "RES"))
    )
    (comp (ref "Y2")
      (value "ASEMPC-40.000MHZ-XR-T")
      (footprint "FP-ASEMP-CMOS-MFG")
      (description "MEMS Oscillator 40MHz ±25ppm CMOS 2.25V~3.6V 6-SMD 3.2mm x 2.5mm")
      (libsource (lib "Altium Content Vault") (part "9526c112e3a98a1af86e8f4e974a861"))
    )
  )
  (nets
    (net (code "1") (name "+3.3V") (class "Default")
      (node (ref "C118") (pin "1") (pinfunction "1_1") (pintype "passive"))
      (node (ref "C119") (pin "1") (pinfunction "1_1") (pintype "passive"))
      (node (ref "C131") (pin "1") (pinfunction "1_1") (pintype "passive"))
      (node (ref "C132") (pin "1") (pinfunction "1_1") (pintype "passive"))
      (node (ref "C136") (pin "1") (pinfunction "1_1") (pintype "passive"))
      (node (ref "C139") (pin "1") (pinfunction "1_1") (pintype "passive"))
      (node (ref "C140") (pin "1") (pinfunction "1_1") (pintype "passive"))
      (node (ref "C150") (pin "1") (pinfunction "1_1") (pintype "passive"))
      (node (ref "C154") (pin "1") (pinfunction "1_1") (pintype "passive"))
      (node (ref "C155") (pin "1") (pinfunction "1_1") (pintype "passive"))
      (node (ref "C158") (pin "1") (pinfunction "1_1") (pintype "passive"))
      (node (ref "C159") (pin "1") (pinfunction "1_1") (pintype "passive"))
      (node (ref "C167") (pin "1") (pinfunction "1_1") (pintype "passive"))
      (node (ref "C168") (pin "1") (pinfunction "1_1") (pintype "passive"))
      (node (ref "C169") (pin "1") (pinfunction "1_1") (pintype "passive"))
      (node (ref "C172") (pin "1") (pinfunction "1_1") (pintype "passive"))
      (node (ref "C173") (pin "1") (pinfunction "1_1") (pintype "passive"))
      (node (ref "C181") (pin "1") (pinfunction "1_1") (pintype "passive"))
      (node (ref "C182") (pin "1") (pinfunction "1_1") (pintype "passive"))
      (node (ref "C183") (pin "1") (pinfunction "1_1") (pintype "passive"))
      (node (ref "C186") (pin "1") (pinfunction "1_1") (pintype "passive"))
      (node (ref "C187") (pin "1") (pinfunction "1_1") (pintype "passive"))
      (node (ref "C191") (pin "1") (pinfunction "1_1") (pintype "passive"))
      (node (ref "C192") (pin "1") (pinfunction "1_1") (pintype "passive"))
      (node (ref "L1") (pin "1") (pinfunction "1_1") (pintype "passive"))
      (node (ref "L11") (pin "1") (pinfunction "1_1") (pintype "passive"))
      (node (ref "L12") (pin "1") (pinfunction "1_1") (pintype "passive"))
      (node (ref "L13") (pin "1") (pinfunction "1_1") (pintype "passive"))
      (node (ref "L15") (pin "1") (pinfunction "1_1") (pintype "passive"))
      (node (ref "L16") (pin "1") (pinfunction "1_1") (pintype "passive"))
      (node (ref "L17") (pin "1") (pinfunction "1_1") (pintype "passive"))
      (node (ref "L18") (pin "1") (pinfunction "1_1") (pintype "passive"))
      (node (ref "L2") (pin "1") (pinfunction "1_1") (pintype "passive"))
      (node (ref "L5") (pin "1") (pinfunction "1_1") (pintype "passive"))
      (node (ref "L6") (pin "1") (pinfunction "1_1") (pintype "passive"))
      (node (ref "L8") (pin "1") (pinfunction "1_1") (pintype "passive"))
      (node (ref "L9") (pin "1") (pinfunction "1_1") (pintype "passive"))
      (node (ref "R194") (pin "1") (pinfunction "1_1") (pintype "passive"))
      (node (ref "R195") (pin "2") (pinfunction "2_2") (pintype "passive"))
    )
    (net (code "2") (name "DPLL_OSCI") (class "Default")
      (node (ref "C190") (pin "2") (pinfunction "2_2") (pintype "passive"))
    )
    (net (code "3") (name "DPLL_VDDA_BG_LC") (class "Default")
      (node (ref "C128") (pin "1") (pinfunction "1_1") (pintype "passive"))
      (node (ref "C129") (pin "1") (pinfunction "1_1") (pintype "passive"))
      (node (ref "C130") (pin "1") (pinfunction "1_1") (pintype "passive"))
      (node (ref "L2") (pin "2") (pinfunction "2_2") (pintype "passive"))
    )
    (net (code "4") (name "DPLL_VDDA_FB") (class "Default")
      (node (ref "C174") (pin "1") (pinfunction "1_1") (pintype "passive"))
      (node (ref "C175") (pin "1") (pinfunction "1_1") (pintype "passive"))
      (node (ref "L14") (pin "2") (pinfunction "2_2") (pintype "passive"))
    )
    (net (code "5") (name "DPLL_VDDA_PDCP_XTAL") (class "Default")
      (node (ref "C148") (pin "1") (pinfunction "1_1") (pintype "passive"))
      (node (ref "C149") (pin "1") (pinfunction "1_1") (pintype "passive"))
      (node (ref "L6") (pin "2") (pinfunction "2_2") (pintype "passive"))
    )
    (net (code "6") (name "DPLL_VDDO_Q0") (class "Default")
      (node (ref "C160") (pin "1") (pinfunction "1_1") (pintype "passive"))
      (node (ref "C161") (pin "1") (pinfunction "1_1") (pintype "passive"))
      (node (ref "L9") (pin "2") (pinfunction "2_2") (pintype "passive"))
    )
    (net (code "7") (name "DPLL_VDDO_Q1") (class "Default")
      (node (ref "C176") (pin "1") (pinfunction "1_1") (pintype "passive"))
      (node (ref "C177") (pin "1") (pinfunction "1_1") (pintype "passive"))
      (node (ref "L13") (pin "2") (pinfunction "2_2") (pintype "passive"))
    )
    (net (code "8") (name "DPLL_VDDO_Q2") (class "Default")
      (node (ref "C184") (pin "1") (pinfunction "1_1") (pintype "passive"))
      (node (ref "C185") (pin "1") (pinfunction "1_1") (pintype "passive"))
      (node (ref "L16") (pin "2") (pinfunction "2_2") (pintype "passive"))
    )
    (net (code "9") (name "DPLL_VDDO_Q3") (class "Default")
      (node (ref "C188") (pin "1") (pinfunction "1_1") (pintype "passive"))
      (node (ref "C189") (pin "1") (pinfunction "1_1") (pintype "passive"))
      (node (ref "L17") (pin "2") (pinfunction "2_2") (pintype "passive"))
    )
    (net (code "10") (name "DPLL_VDDO_Q4") (class "Default")
      (node (ref "C120") (pin "1") (pinfunction "1_1") (pintype "passive"))
      (node (ref "C121") (pin "1") (pinfunction "1_1") (pintype "passive"))
      (node (ref "L1") (pin "2") (pinfunction "2_2") (pintype "passive"))
    )
    (net (code "11") (name "DPLL_VDDO_Q5") (class "Default")
      (node (ref "C141") (pin "1") (pinfunction "1_1") (pintype "passive"))
      (node (ref "C142") (pin "1") (pinfunction "1_1") (pintype "passive"))
      (node (ref "L5") (pin "2") (pinfunction "2_2") (pintype "passive"))
    )
    (net (code "12") (name "DPLL_VDDO_Q6") (class "Default")
      (node (ref "C156") (pin "1") (pinfunction "1_1") (pintype "passive"))
      (node (ref "C157") (pin "1") (pinfunction "1_1") (pintype "passive"))
      (node (ref "L8") (pin "2") (pinfunction "2_2") (pintype "passive"))
    )
    (net (code "13") (name "DPLL_VDDO_Q7") (class "Default")
      (node (ref "C170") (pin "1") (pinfunction "1_1") (pintype "passive"))
      (node (ref "C171") (pin "1") (pinfunction "1_1") (pintype "passive"))
      (node (ref "L12") (pin "2") (pinfunction "2_2") (pintype "passive"))
    )
    (net (code "14") (name "DPLL_VDD_CLKA") (class "Default")
      (node (ref "C179") (pin "1") (pinfunction "1_1") (pintype "passive"))
      (node (ref "C180") (pin "1") (pinfunction "1_1") (pintype "passive"))
      (node (ref "L15") (pin "2") (pinfunction "2_2") (pintype "passive"))
    )
    (net (code "15") (name "DPLL_VDD_CLKB") (class "Default")
      (node (ref "C165") (pin "1") (pinfunction "1_1") (pintype "passive"))
      (node (ref "C166") (pin "1") (pinfunction "1_1") (pintype "passive"))
      (node (ref "L11") (pin "2") (pinfunction "2_2") (pintype "passive"))
    )
    (net (code "16") (name "DPLL_VDD_DCO_Q0123") (class "Default")
      (node (ref "C151") (pin "1") (pinfunction "1_1") (pintype "passive"))
      (node (ref "C152") (pin "1") (pinfunction "1_1") (pintype "passive"))
      (node (ref "L7") (pin "2") (pinfunction "2_2") (pintype "passive"))
    )
    (net (code "17") (name "DPLL_VDD_DCO_Q4567") (class "Default")
      (node (ref "C162") (pin "1") (pinfunction "1_1") (pintype "passive"))
      (node (ref "C163") (pin "1") (pinfunction "1_1") (pintype "passive"))
      (node (ref "L10") (pin "2") (pinfunction "2_2") (pintype "passive"))
    )
    (net (code "18") (name "DPLL_VDD_DIA_A") (class "Default")
      (node (ref "C122") (pin "1") (pinfunction "1_1") (pintype "passive"))
      (node (ref "C123") (pin "1") (pinfunction "1_1") (pintype "passive"))
      (node (ref "L3") (pin "2") (pinfunction "2_2") (pintype "passive"))
    )
    (net (code "19") (name "DPLL_VDD_DIA_B") (class "Default")
      (node (ref "C137") (pin "1") (pinfunction "1_1") (pintype "passive"))
      (node (ref "C138") (pin "1") (pinfunction "1_1") (pintype "passive"))
      (node (ref "L4") (pin "2") (pinfunction "2_2") (pintype "passive"))
    )
    (net (code "20") (name "DPLL_VDD_DIG") (class "Default")
      (node (ref "C124") (pin "1") (pinfunction "1_1") (pintype "passive"))
      (node (ref "C125") (pin "1") (pinfunction "1_1") (pintype "passive"))
      (node (ref "C126") (pin "1") (pinfunction "1_1") (pintype "passive"))
      (node (ref "C127") (pin "1") (pinfunction "1_1") (pintype "passive"))
      (node (ref "R193") (pin "2") (pinfunction "2_2") (pintype "passive"))
    )
    (net (code "21") (name "DPLL_VDD_GPIO") (class "Default")
      (node (ref "C144") (pin "1") (pinfunction "1_1") (pintype "passive"))
      (node (ref "C145") (pin "1") (pinfunction "1_1") (pintype "passive"))
      (node (ref "C146") (pin "1") (pinfunction "1_1") (pintype "passive"))
      (node (ref "C147") (pin "1") (pinfunction "1_1") (pintype "passive"))
      (node (ref "R194") (pin "2") (pinfunction "2_2") (pintype "passive"))
    )
    (net (code "22") (name "GND") (class "Default")
      (node (ref "C118") (pin "2") (pinfunction "2_2") (pintype "passive"))
      (node (ref "C119") (pin "2") (pinfunction "2_2") (pintype "passive"))
      (node (ref "C120") (pin "2") (pinfunction "2_2") (pintype "passive"))
      (node (ref "C121") (pin "2") (pinfunction "2_2") (pintype "passive"))
      (node (ref "C122") (pin "2") (pinfunction "2_2") (pintype "passive"))
      (node (ref "C123") (pin "2") (pinfunction "2_2") (pintype "passive"))
      (node (ref "C124") (pin "2") (pinfunction "2_2") (pintype "passive"))
      (node (ref "C125") (pin "2") (pinfunction "2_2") (pintype "passive"))
      (node (ref "C126") (pin "2") (pinfunction "2_2") (pintype "passive"))
      (node (ref "C127") (pin "2") (pinfunction "2_2") (pintype "passive"))
      (node (ref "C128") (pin "2") (pinfunction "2_2") (pintype "passive"))
      (node (ref "C129") (pin "2") (pinfunction "2_2") (pintype "passive"))
      (node (ref "C130") (pin "2") (pinfunction "2_2") (pintype "passive"))
      (node (ref "C131") (pin "2") (pinfunction "2_2") (pintype "passive"))
      (node (ref "C132") (pin "2") (pinfunction "2_2") (pintype "passive"))
      (node (ref "C133") (pin "2") (pinfunction "2_2") (pintype "passive"))
      (node (ref "C134") (pin "2") (pinfunction "2_2") (pintype "passive"))
      (node (ref "C135") (pin "2") (pinfunction "2_2") (pintype "passive"))
      (node (ref "C136") (pin "2") (pinfunction "2_2") (pintype "passive"))
      (node (ref "C137") (pin "2") (pinfunction "2_2") (pintype "passive"))
      (node (ref "C138") (pin "2") (pinfunction "2_2") (pintype "passive"))
      (node (ref "C139") (pin "2") (pinfunction "2_2") (pintype "passive"))
      (node (ref "C140") (pin "2") (pinfunction "2_2") (pintype "passive"))
      (node (ref "C141") (pin "2") (pinfunction "2_2") (pintype "passive"))
      (node (ref "C142") (pin "2") (pinfunction "2_2") (pintype "passive"))
      (node (ref "C143") (pin "2") (pinfunction "2_2") (pintype "passive"))
      (node (ref "C144") (pin "2") (pinfunction "2_2") (pintype "passive"))
      (node (ref "C145") (pin "2") (pinfunction "2_2") (pintype "passive"))
      (node (ref "C146") (pin "2") (pinfunction "2_2") (pintype "passive"))
      (node (ref "C147") (pin "2") (pinfunction "2_2") (pintype "passive"))
      (node (ref "C148") (pin "2") (pinfunction "2_2") (pintype "passive"))
      (node (ref "C149") (pin "2") (pinfunction "2_2") (pintype "passive"))
      (node (ref "C150") (pin "2") (pinfunction "2_2") (pintype "passive"))
      (node (ref "C151") (pin "2") (pinfunction "2_2") (pintype "passive"))
      (node (ref "C152") (pin "2") (pinfunction "2_2") (pintype "passive"))
      (node (ref "C153") (pin "2") (pinfunction "2_2") (pintype "passive"))
      (node (ref "C154") (pin "2") (pinfunction "2_2") (pintype "passive"))
      (node (ref "C155") (pin "2") (pinfunction "2_2") (pintype "passive"))
      (node (ref "C156") (pin "2") (pinfunction "2_2") (pintype "passive"))
      (node (ref "C157") (pin "2") (pinfunction "2_2") (pintype "passive"))
      (node (ref "C158") (pin "2") (pinfunction "2_2") (pintype "passive"))
      (node (ref "C159") (pin "2") (pinfunction "2_2") (pintype "passive"))
      (node (ref "C160") (pin "2") (pinfunction "2_2") (pintype "passive"))
      (node (ref "C161") (pin "2") (pinfunction "2_2") (pintype "passive"))
      (node (ref "C162") (pin "2") (pinfunction "2_2") (pintype "passive"))
      (node (ref "C163") (pin "2") (pinfunction "2_2") (pintype "passive"))
      (node (ref "C164") (pin "2") (pinfunction "2_2") (pintype "passive"))
      (node (ref "C165") (pin "2") (pinfunction "2_2") (pintype "passive"))
      (node (ref "C166") (pin "2") (pinfunction "2_2") (pintype "passive"))
      (node (ref "C167") (pin "2") (pinfunction "2_2") (pintype "passive"))
      (node (ref "C168") (pin "2") (pinfunction "2_2") (pintype "passive"))
      (node (ref "C169") (pin "2") (pinfunction "2_2") (pintype "passive"))
      (node (ref "C170") (pin "2") (pinfunction "2_2") (pintype "passive"))
      (node (ref "C171") (pin "2") (pinfunction "2_2") (pintype "passive"))
      (node (ref "C172") (pin "2") (pinfunction "2_2") (pintype "passive"))
      (node (ref "C173") (pin "2") (pinfunction "2_2") (pintype "passive"))
      (node (ref "C174") (pin "2") (pinfunction "2_2") (pintype "passive"))
      (node (ref "C175") (pin "2") (pinfunction "2_2") (pintype "passive"))
      (node (ref "C176") (pin "2") (pinfunction "2_2") (pintype "passive"))
      (node (ref "C177") (pin "2") (pinfunction "2_2") (pintype "passive"))
      (node (ref "C178") (pin "2") (pinfunction "2_2") (pintype "passive"))
      (node (ref "C179") (pin "2") (pinfunction "2_2") (pintype "passive"))
      (node (ref "C180") (pin "2") (pinfunction "2_2") (pintype "passive"))
      (node (ref "C181") (pin "2") (pinfunction "2_2") (pintype "passive"))
      (node (ref "C182") (pin "2") (pinfunction "2_2") (pintype "passive"))
      (node (ref "C183") (pin "2") (pinfunction "2_2") (pintype "passive"))
      (node (ref "C184") (pin "2") (pinfunction "2_2") (pintype "passive"))
      (node (ref "C185") (pin "2") (pinfunction "2_2") (pintype "passive"))
      (node (ref "C186") (pin "2") (pinfunction "2_2") (pintype "passive"))
      (node (ref "C187") (pin "2") (pinfunction "2_2") (pintype "passive"))
      (node (ref "C188") (pin "2") (pinfunction "2_2") (pintype "passive"))
      (node (ref "C189") (pin "2") (pinfunction "2_2") (pintype "passive"))
      (node (ref "C191") (pin "2") (pinfunction "2_2") (pintype "passive"))
      (node (ref "C192") (pin "2") (pinfunction "2_2") (pintype "passive"))
      (node (ref "C193") (pin "2") (pinfunction "2_2") (pintype "passive"))
      (node (ref "C194") (pin "2") (pinfunction "2_2") (pintype "passive"))
      (node (ref "R197") (pin "1") (pinfunction "1_1") (pintype "passive"))
      (node (ref "Y2") (pin "3") (pinfunction "GND_3") (pintype "power_in"))
    )
    (net (code "23") (name "Net-(C190-Pad1)") (class "Default")
      (node (ref "C190") (pin "1") (pinfunction "1_1") (pintype "passive"))
      (node (ref "R195") (pin "1") (pinfunction "1_1") (pintype "passive"))
      (node (ref "R196") (pin "2") (pinfunction "2_2") (pintype "passive"))
      (node (ref "R197") (pin "2") (pinfunction "2_2") (pintype "passive"))
    )
    (net (code "24") (name "Net-(Y2-Output)") (class "Default")
      (node (ref "R196") (pin "1") (pinfunction "1_1") (pintype "passive"))
      (node (ref "Y2") (pin "4") (pinfunction "Output_4") (pintype "output"))
    )
    (net (code "25") (name "Net-(Y2-VDD)") (class "Default")
      (node (ref "C193") (pin "1") (pinfunction "1_1") (pintype "passive"))
      (node (ref "C194") (pin "1") (pinfunction "1_1") (pintype "passive"))
      (node (ref "L18") (pin "2") (pinfunction "2_2") (pintype "passive"))
      (node (ref "Y2") (pin "1") (pinfunction "~{Tri-State}_1") (pintype "input"))
      (node (ref "Y2") (pin "6") (pinfunction "VDD_6") (pintype "power_in"))
    )
    (net (code "26") (name "P1V8") (class "Default")
      (node (ref "C133") (pin "1") (pinfunction "1_1") (pintype "passive"))
      (node (ref "C134") (pin "1") (pinfunction "1_1") (pintype "passive"))
      (node (ref "C135") (pin "1") (pinfunction "1_1") (pintype "passive"))
      (node (ref "C143") (pin "1") (pinfunction "1_1") (pintype "passive"))
      (node (ref "C153") (pin "1") (pinfunction "1_1") (pintype "passive"))
      (node (ref "C164") (pin "1") (pinfunction "1_1") (pintype "passive"))
      (node (ref "C178") (pin "1") (pinfunction "1_1") (pintype "passive"))
      (node (ref "L10") (pin "1") (pinfunction "1_1") (pintype "passive"))
      (node (ref "L14") (pin "1") (pinfunction "1_1") (pintype "passive"))
      (node (ref "L3") (pin "1") (pinfunction "1_1") (pintype "passive"))
      (node (ref "L4") (pin "1") (pinfunction "1_1") (pintype "passive"))
      (node (ref "L7") (pin "1") (pinfunction "1_1") (pintype "passive"))
      (node (ref "R193") (pin "1") (pinfunction "1_1") (pintype "passive"))
    )
  )
)
